# interface.net
KiCad netlist of a schematic drawn in EAGLE
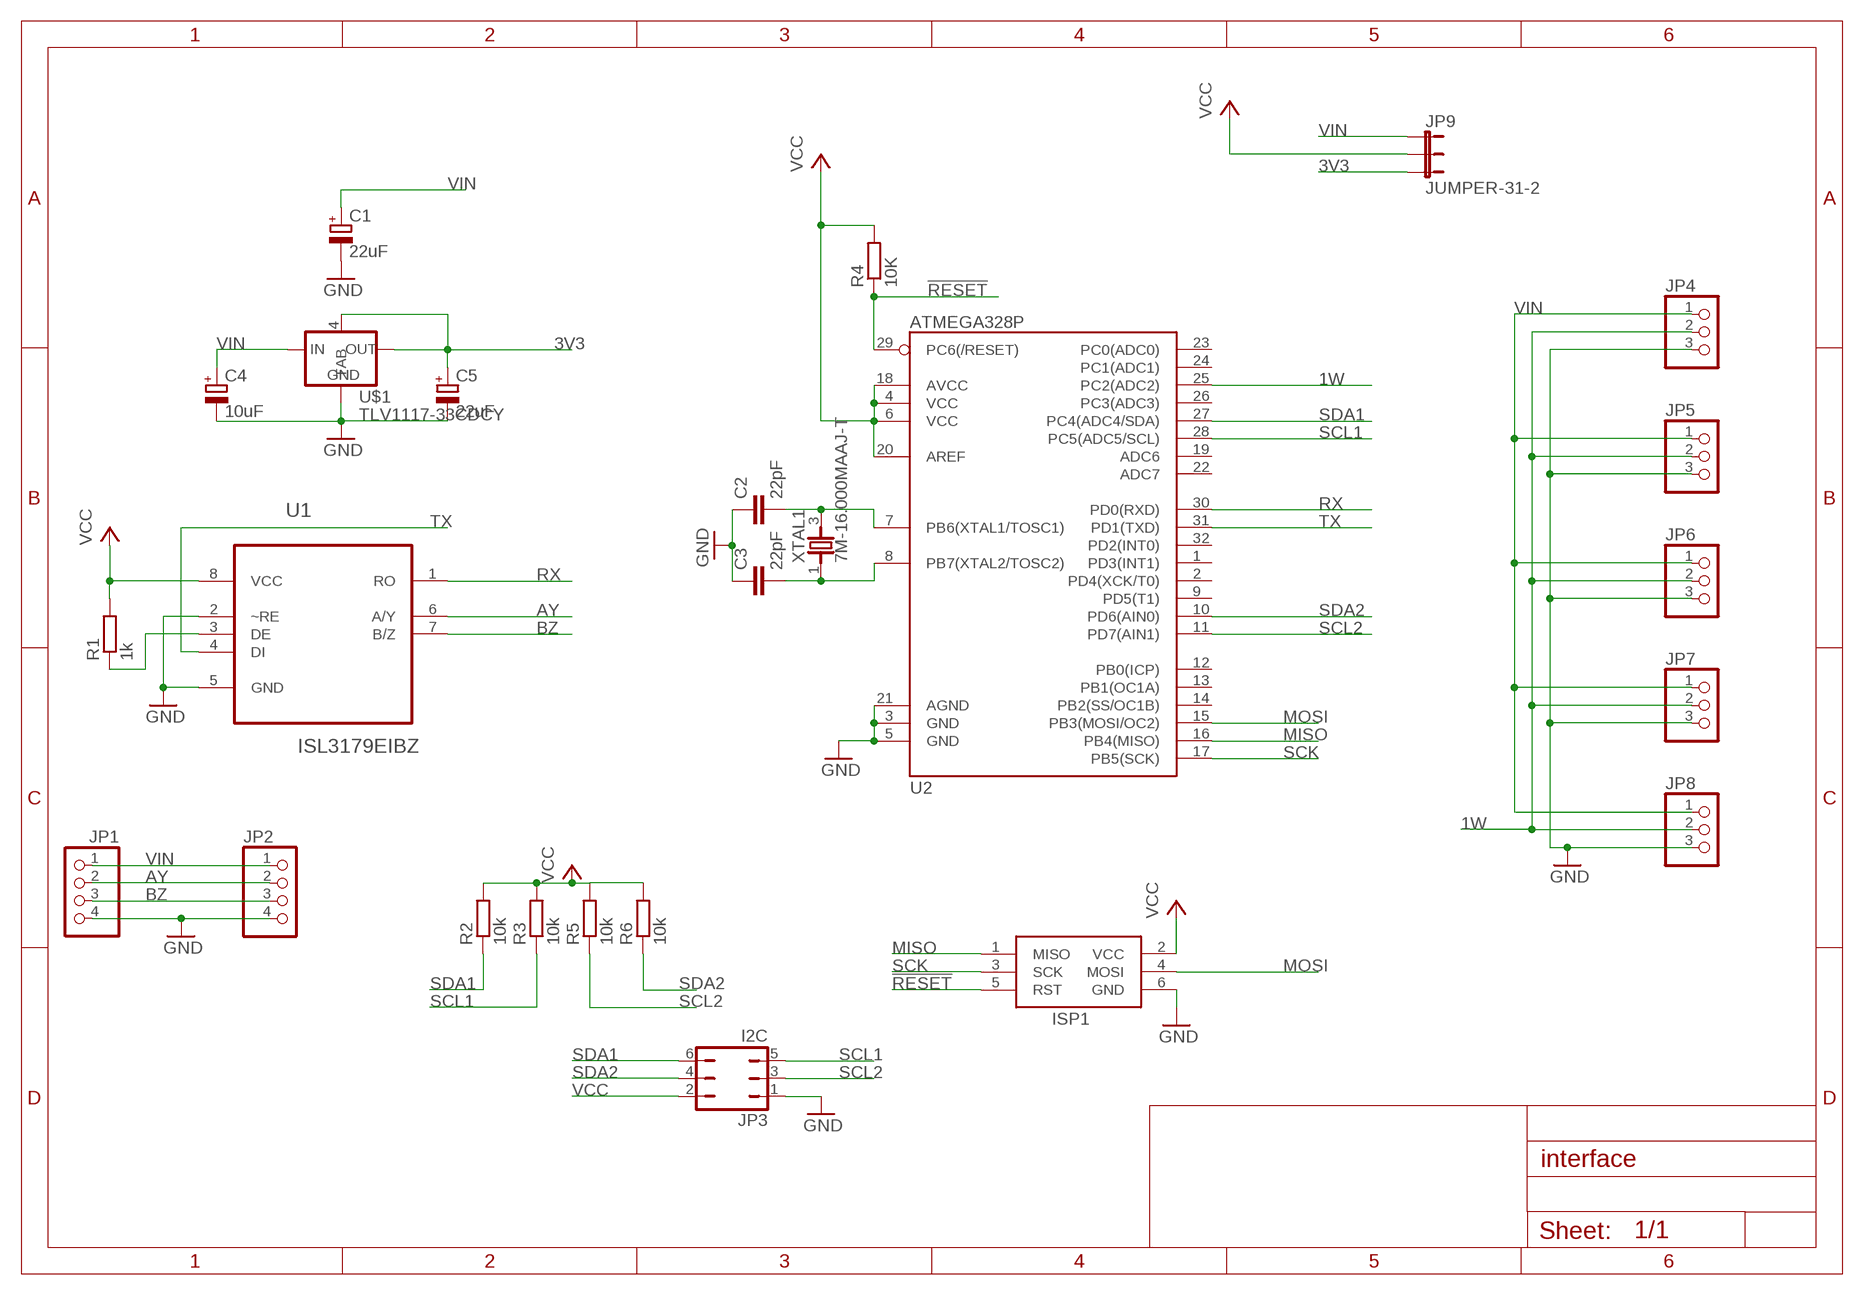
[diagram p0: schematic, sheet 1]

(export (version "E")
  (design (tool "Eeschema 10.0.6"))
  (components
    (comp (ref "C1")
      (value "22uF")
      (footprint "eagle-import:A_3216-18R")
      (libsource (lib "eagle-import") (part "CPOL-EUA/3216-18R"))
    )
    (comp (ref "C2")
      (value "22pF")
      (footprint "eagle-import:C0805")
      (libsource (lib "eagle-import") (part "C-EUC0805"))
    )
    (comp (ref "C3")
      (value "22pF")
      (footprint "eagle-import:C0805")
      (libsource (lib "eagle-import") (part "C-EUC0805"))
    )
    (comp (ref "C4")
      (value "10uF")
      (footprint "eagle-import:A_3216-18R")
      (libsource (lib "eagle-import") (part "CPOL-EUA/3216-18R"))
    )
    (comp (ref "C5")
      (value "22uF")
      (footprint "eagle-import:A_3216-18R")
      (libsource (lib "eagle-import") (part "CPOL-EUA/3216-18R"))
    )
    (comp (ref "ISP1")
      (value "AVRISP-6")
      (footprint "eagle-import:AVRISP")
      (libsource (lib "eagle-import") (part "AVRISP-6"))
    )
    (comp (ref "JP1")
      (value "PINHD-1X4")
      (footprint "eagle-import:1X04")
      (libsource (lib "eagle-import") (part "PINHD-1X4"))
    )
    (comp (ref "JP2")
      (value "PINHD-1X4")
      (footprint "eagle-import:1X04")
      (libsource (lib "eagle-import") (part "PINHD-1X4"))
    )
    (comp (ref "JP3")
      (value "I2C")
      (footprint "eagle-import:JP3Q")
      (libsource (lib "eagle-import") (part "JP3Q"))
    )
    (comp (ref "JP4")
      (value "PINHD-1X3")
      (footprint "eagle-import:1X03")
      (libsource (lib "eagle-import") (part "PINHD-1X3"))
    )
    (comp (ref "JP5")
      (value "PINHD-1X3")
      (footprint "eagle-import:1X03")
      (libsource (lib "eagle-import") (part "PINHD-1X3"))
    )
    (comp (ref "JP6")
      (value "PINHD-1X3")
      (footprint "eagle-import:1X03")
      (libsource (lib "eagle-import") (part "PINHD-1X3"))
    )
    (comp (ref "JP7")
      (value "PINHD-1X3")
      (footprint "eagle-import:1X03")
      (libsource (lib "eagle-import") (part "PINHD-1X3"))
    )
    (comp (ref "JP8")
      (value "PINHD-1X3")
      (footprint "eagle-import:1X03")
      (libsource (lib "eagle-import") (part "PINHD-1X3"))
    )
    (comp (ref "JP9")
      (value "JUMPER-31-2")
      (footprint "eagle-import:SJ_3_PASTE1&2")
      (libsource (lib "eagle-import") (part "JUMPER-31-2"))
    )
    (comp (ref "R1")
      (value "1k")
      (footprint "eagle-import:R0805")
      (libsource (lib "eagle-import") (part "R-EU_R0805"))
    )
    (comp (ref "R2")
      (value "10k")
      (footprint "eagle-import:R0805")
      (libsource (lib "eagle-import") (part "R-EU_R0805"))
    )
    (comp (ref "R3")
      (value "10k")
      (footprint "eagle-import:R0805")
      (libsource (lib "eagle-import") (part "R-EU_R0805"))
    )
    (comp (ref "R4")
      (value "10K")
      (footprint "eagle-import:R0805")
      (libsource (lib "eagle-import") (part "R-EU_R0805"))
    )
    (comp (ref "R5")
      (value "10k")
      (footprint "eagle-import:R0805")
      (libsource (lib "eagle-import") (part "R-EU_R0805"))
    )
    (comp (ref "R6")
      (value "10k")
      (footprint "eagle-import:R0805")
      (libsource (lib "eagle-import") (part "R-EU_R0805"))
    )
    (comp (ref "U$1")
      (value "TLV1117-33CDCY")
      (footprint "eagle-import:SOT223")
      (libsource (lib "eagle-import") (part "TLV1117-33CDCY"))
    )
    (comp (ref "U1")
      (value "ISL3179EIBZ")
      (footprint "eagle-import:SOIC127P600X175-8N")
      (libsource (lib "eagle-import") (part "ISL3179EIBZ"))
    )
    (comp (ref "U2")
      (value "ATMEGA328P")
      (footprint "eagle-import:TQFP32-08")
      (libsource (lib "eagle-import") (part "ATMEGA328_SMT"))
    )
    (comp (ref "XTAL1")
      (value "7M-16.000MAAJ-T")
      (footprint "eagle-import:TXC_7M-16.000MAAJ-T")
      (fields (field (name "MPN") "7M-16.000MAAJ-T "))
      (libsource (lib "eagle-import") (part "7M-16.000MAAJ-T"))
    )
  )
  (nets
    (net (code "1") (name "/1W") (class "Default")
      (node (ref "JP4") (pin "2") (pinfunction "2_2") (pintype "passive"))
      (node (ref "JP5") (pin "2") (pinfunction "2_2") (pintype "passive"))
      (node (ref "JP6") (pin "2") (pinfunction "2_2") (pintype "passive"))
      (node (ref "JP7") (pin "2") (pinfunction "2_2") (pintype "passive"))
      (node (ref "JP8") (pin "2") (pinfunction "2_2") (pintype "passive"))
      (node (ref "U2") (pin "25") (pinfunction "PC2(ADC2)_25") (pintype "bidirectional"))
    )
    (net (code "2") (name "/3V3") (class "Default")
      (node (ref "C5") (pin "+") (pinfunction "+_+") (pintype "passive"))
      (node (ref "JP9") (pin "3") (pinfunction "3_3") (pintype "passive"))
      (node (ref "U$1") (pin "2") (pinfunction "OUT_2") (pintype "passive"))
      (node (ref "U$1") (pin "4") (pinfunction "TAB_4") (pintype "passive"))
    )
    (net (code "3") (name "/AY") (class "Default")
      (node (ref "JP1") (pin "2") (pinfunction "2_2") (pintype "passive"))
      (node (ref "JP2") (pin "2") (pinfunction "2_2") (pintype "passive"))
      (node (ref "U1") (pin "6") (pinfunction "A/Y_6") (pintype "bidirectional"))
    )
    (net (code "4") (name "/BZ") (class "Default")
      (node (ref "JP1") (pin "3") (pinfunction "3_3") (pintype "passive"))
      (node (ref "JP2") (pin "3") (pinfunction "3_3") (pintype "passive"))
      (node (ref "U1") (pin "7") (pinfunction "B/Z_7") (pintype "bidirectional"))
    )
    (net (code "5") (name "/MISO") (class "Default")
      (node (ref "ISP1") (pin "1") (pinfunction "MISO_1") (pintype "input"))
      (node (ref "U2") (pin "16") (pinfunction "PB4(MISO)_16") (pintype "bidirectional"))
    )
    (net (code "6") (name "/MOSI") (class "Default")
      (node (ref "ISP1") (pin "4") (pinfunction "MOSI_4") (pintype "output"))
      (node (ref "U2") (pin "15") (pinfunction "PB3(MOSI/OC2)_15") (pintype "bidirectional"))
    )
    (net (code "7") (name "/RX") (class "Default")
      (node (ref "U1") (pin "1") (pinfunction "RO_1") (pintype "output"))
      (node (ref "U2") (pin "30") (pinfunction "PD0(RXD)_30") (pintype "bidirectional"))
    )
    (net (code "8") (name "/SCK") (class "Default")
      (node (ref "ISP1") (pin "3") (pinfunction "SCK_3") (pintype "output"))
      (node (ref "U2") (pin "17") (pinfunction "PB5(SCK)_17") (pintype "bidirectional"))
    )
    (net (code "9") (name "/SCL1") (class "Default")
      (node (ref "JP3") (pin "5") (pinfunction "5_5") (pintype "passive"))
      (node (ref "R3") (pin "1") (pinfunction "1_1") (pintype "passive"))
      (node (ref "U2") (pin "28") (pinfunction "PC5(ADC5/SCL)_28") (pintype "bidirectional"))
    )
    (net (code "10") (name "/SCL2") (class "Default")
      (node (ref "JP3") (pin "3") (pinfunction "3_3") (pintype "passive"))
      (node (ref "R5") (pin "1") (pinfunction "1_1") (pintype "passive"))
      (node (ref "U2") (pin "11") (pinfunction "PD7(AIN1)_11") (pintype "bidirectional"))
    )
    (net (code "11") (name "/SDA1") (class "Default")
      (node (ref "JP3") (pin "6") (pinfunction "6_6") (pintype "passive"))
      (node (ref "R2") (pin "1") (pinfunction "1_1") (pintype "passive"))
      (node (ref "U2") (pin "27") (pinfunction "PC4(ADC4/SDA)_27") (pintype "bidirectional"))
    )
    (net (code "12") (name "/SDA2") (class "Default")
      (node (ref "JP3") (pin "4") (pinfunction "4_4") (pintype "passive"))
      (node (ref "R6") (pin "1") (pinfunction "1_1") (pintype "passive"))
      (node (ref "U2") (pin "10") (pinfunction "PD6(AIN0)_10") (pintype "bidirectional"))
    )
    (net (code "13") (name "/TX") (class "Default")
      (node (ref "U1") (pin "4") (pinfunction "DI_4") (pintype "input"))
      (node (ref "U2") (pin "31") (pinfunction "PD1(TXD)_31") (pintype "bidirectional"))
    )
    (net (code "14") (name "/VIN") (class "Default")
      (node (ref "C1") (pin "+") (pinfunction "+_+") (pintype "passive"))
      (node (ref "C4") (pin "+") (pinfunction "+_+") (pintype "passive"))
      (node (ref "JP1") (pin "1") (pinfunction "1_1") (pintype "passive"))
      (node (ref "JP2") (pin "1") (pinfunction "1_1") (pintype "passive"))
      (node (ref "JP4") (pin "1") (pinfunction "1_1") (pintype "passive"))
      (node (ref "JP5") (pin "1") (pinfunction "1_1") (pintype "passive"))
      (node (ref "JP6") (pin "1") (pinfunction "1_1") (pintype "passive"))
      (node (ref "JP7") (pin "1") (pinfunction "1_1") (pintype "passive"))
      (node (ref "JP8") (pin "1") (pinfunction "1_1") (pintype "passive"))
      (node (ref "JP9") (pin "1") (pinfunction "1_1") (pintype "passive"))
      (node (ref "U$1") (pin "3") (pinfunction "IN_3") (pintype "input"))
    )
    (net (code "15") (name "/~{RESET}") (class "Default")
      (node (ref "ISP1") (pin "5") (pinfunction "RST_5") (pintype "output"))
      (node (ref "R4") (pin "1") (pinfunction "1_1") (pintype "passive"))
      (node (ref "U2") (pin "29") (pinfunction "PC6(/RESET)_29") (pintype "bidirectional"))
    )
    (net (code "16") (name "GND") (class "Default")
      (node (ref "C1") (pin "-") (pinfunction "-_-") (pintype "passive"))
      (node (ref "C2") (pin "1") (pinfunction "1_1") (pintype "passive"))
      (node (ref "C3") (pin "1") (pinfunction "1_1") (pintype "passive"))
      (node (ref "C4") (pin "-") (pinfunction "-_-") (pintype "passive"))
      (node (ref "C5") (pin "-") (pinfunction "-_-") (pintype "passive"))
      (node (ref "ISP1") (pin "6") (pinfunction "GND_6") (pintype "power_in"))
      (node (ref "JP1") (pin "4") (pinfunction "4_4") (pintype "passive"))
      (node (ref "JP2") (pin "4") (pinfunction "4_4") (pintype "passive"))
      (node (ref "JP3") (pin "1") (pinfunction "1_1") (pintype "passive"))
      (node (ref "JP4") (pin "3") (pinfunction "3_3") (pintype "passive"))
      (node (ref "JP5") (pin "3") (pinfunction "3_3") (pintype "passive"))
      (node (ref "JP6") (pin "3") (pinfunction "3_3") (pintype "passive"))
      (node (ref "JP7") (pin "3") (pinfunction "3_3") (pintype "passive"))
      (node (ref "JP8") (pin "3") (pinfunction "3_3") (pintype "passive"))
      (node (ref "U$1") (pin "1") (pinfunction "GND_1") (pintype "input"))
      (node (ref "U1") (pin "2") (pinfunction "~{RE}_2") (pintype "input"))
      (node (ref "U1") (pin "5") (pinfunction "GND_5") (pintype "passive"))
      (node (ref "U2") (pin "21") (pinfunction "AGND_21") (pintype "bidirectional"))
      (node (ref "U2") (pin "3") (pinfunction "GND_3") (pintype "bidirectional"))
      (node (ref "U2") (pin "5") (pinfunction "GND_5") (pintype "bidirectional"))
    )
    (net (code "17") (name "Net-(U1-DE)") (class "Default")
      (node (ref "R1") (pin "1") (pinfunction "1_1") (pintype "passive"))
      (node (ref "U1") (pin "3") (pinfunction "DE_3") (pintype "input"))
    )
    (net (code "18") (name "Net-(U2-PB6(XTAL1{slash}TOSC1))") (class "Default")
      (node (ref "C2") (pin "2") (pinfunction "2_2") (pintype "passive"))
      (node (ref "U2") (pin "7") (pinfunction "PB6(XTAL1/TOSC1)_7") (pintype "bidirectional"))
      (node (ref "XTAL1") (pin "3") (pinfunction "3_3") (pintype "passive"))
    )
    (net (code "19") (name "Net-(U2-PB7(XTAL2{slash}TOSC2))") (class "Default")
      (node (ref "C3") (pin "2") (pinfunction "2_2") (pintype "passive"))
      (node (ref "U2") (pin "8") (pinfunction "PB7(XTAL2/TOSC2)_8") (pintype "bidirectional"))
      (node (ref "XTAL1") (pin "1") (pinfunction "1_1") (pintype "passive"))
    )
    (net (code "20") (name "VCC") (class "Default")
      (node (ref "ISP1") (pin "2") (pinfunction "VCC_2") (pintype "power_in"))
      (node (ref "JP3") (pin "2") (pinfunction "2_2") (pintype "passive"))
      (node (ref "JP9") (pin "2") (pinfunction "2_2") (pintype "passive"))
      (node (ref "R1") (pin "2") (pinfunction "2_2") (pintype "passive"))
      (node (ref "R2") (pin "2") (pinfunction "2_2") (pintype "passive"))
      (node (ref "R3") (pin "2") (pinfunction "2_2") (pintype "passive"))
      (node (ref "R4") (pin "2") (pinfunction "2_2") (pintype "passive"))
      (node (ref "R5") (pin "2") (pinfunction "2_2") (pintype "passive"))
      (node (ref "R6") (pin "2") (pinfunction "2_2") (pintype "passive"))
      (node (ref "U1") (pin "8") (pinfunction "VCC_8") (pintype "power_in"))
      (node (ref "U2") (pin "18") (pinfunction "AVCC_18") (pintype "bidirectional"))
      (node (ref "U2") (pin "20") (pinfunction "AREF_20") (pintype "bidirectional"))
      (node (ref "U2") (pin "4") (pinfunction "VCC_4") (pintype "bidirectional"))
      (node (ref "U2") (pin "6") (pinfunction "VCC_6") (pintype "bidirectional"))
    )
    (net (code "21") (name "unconnected-(U2-ADC6-Pad19)") (class "Default")
      (node (ref "U2") (pin "19") (pinfunction "ADC6_19") (pintype "bidirectional"))
    )
    (net (code "22") (name "unconnected-(U2-ADC7-Pad22)") (class "Default")
      (node (ref "U2") (pin "22") (pinfunction "ADC7_22") (pintype "bidirectional"))
    )
    (net (code "23") (name "unconnected-(U2-PB0(ICP)-Pad12)") (class "Default")
      (node (ref "U2") (pin "12") (pinfunction "PB0(ICP)_12") (pintype "bidirectional"))
    )
    (net (code "24") (name "unconnected-(U2-PB1(OC1A)-Pad13)") (class "Default")
      (node (ref "U2") (pin "13") (pinfunction "PB1(OC1A)_13") (pintype "bidirectional"))
    )
    (net (code "25") (name "unconnected-(U2-PB2(SS{slash}OC1B)-Pad14)") (class "Default")
      (node (ref "U2") (pin "14") (pinfunction "PB2(SS/OC1B)_14") (pintype "bidirectional"))
    )
    (net (code "26") (name "unconnected-(U2-PC0(ADC0)-Pad23)") (class "Default")
      (node (ref "U2") (pin "23") (pinfunction "PC0(ADC0)_23") (pintype "bidirectional"))
    )
    (net (code "27") (name "unconnected-(U2-PC1(ADC1)-Pad24)") (class "Default")
      (node (ref "U2") (pin "24") (pinfunction "PC1(ADC1)_24") (pintype "bidirectional"))
    )
    (net (code "28") (name "unconnected-(U2-PC3(ADC3)-Pad26)") (class "Default")
      (node (ref "U2") (pin "26") (pinfunction "PC3(ADC3)_26") (pintype "bidirectional"))
    )
    (net (code "29") (name "unconnected-(U2-PD2(INT0)-Pad32)") (class "Default")
      (node (ref "U2") (pin "32") (pinfunction "PD2(INT0)_32") (pintype "bidirectional"))
    )
    (net (code "30") (name "unconnected-(U2-PD3(INT1)-Pad1)") (class "Default")
      (node (ref "U2") (pin "1") (pinfunction "PD3(INT1)_1") (pintype "bidirectional"))
    )
    (net (code "31") (name "unconnected-(U2-PD4(XCK{slash}T0)-Pad2)") (class "Default")
      (node (ref "U2") (pin "2") (pinfunction "PD4(XCK/T0)_2") (pintype "bidirectional"))
    )
    (net (code "32") (name "unconnected-(U2-PD5(T1)-Pad9)") (class "Default")
      (node (ref "U2") (pin "9") (pinfunction "PD5(T1)_9") (pintype "bidirectional"))
    )
  )
)
